# Relay_module.net
KiCad netlist of a schematic drawn in Altium Designer
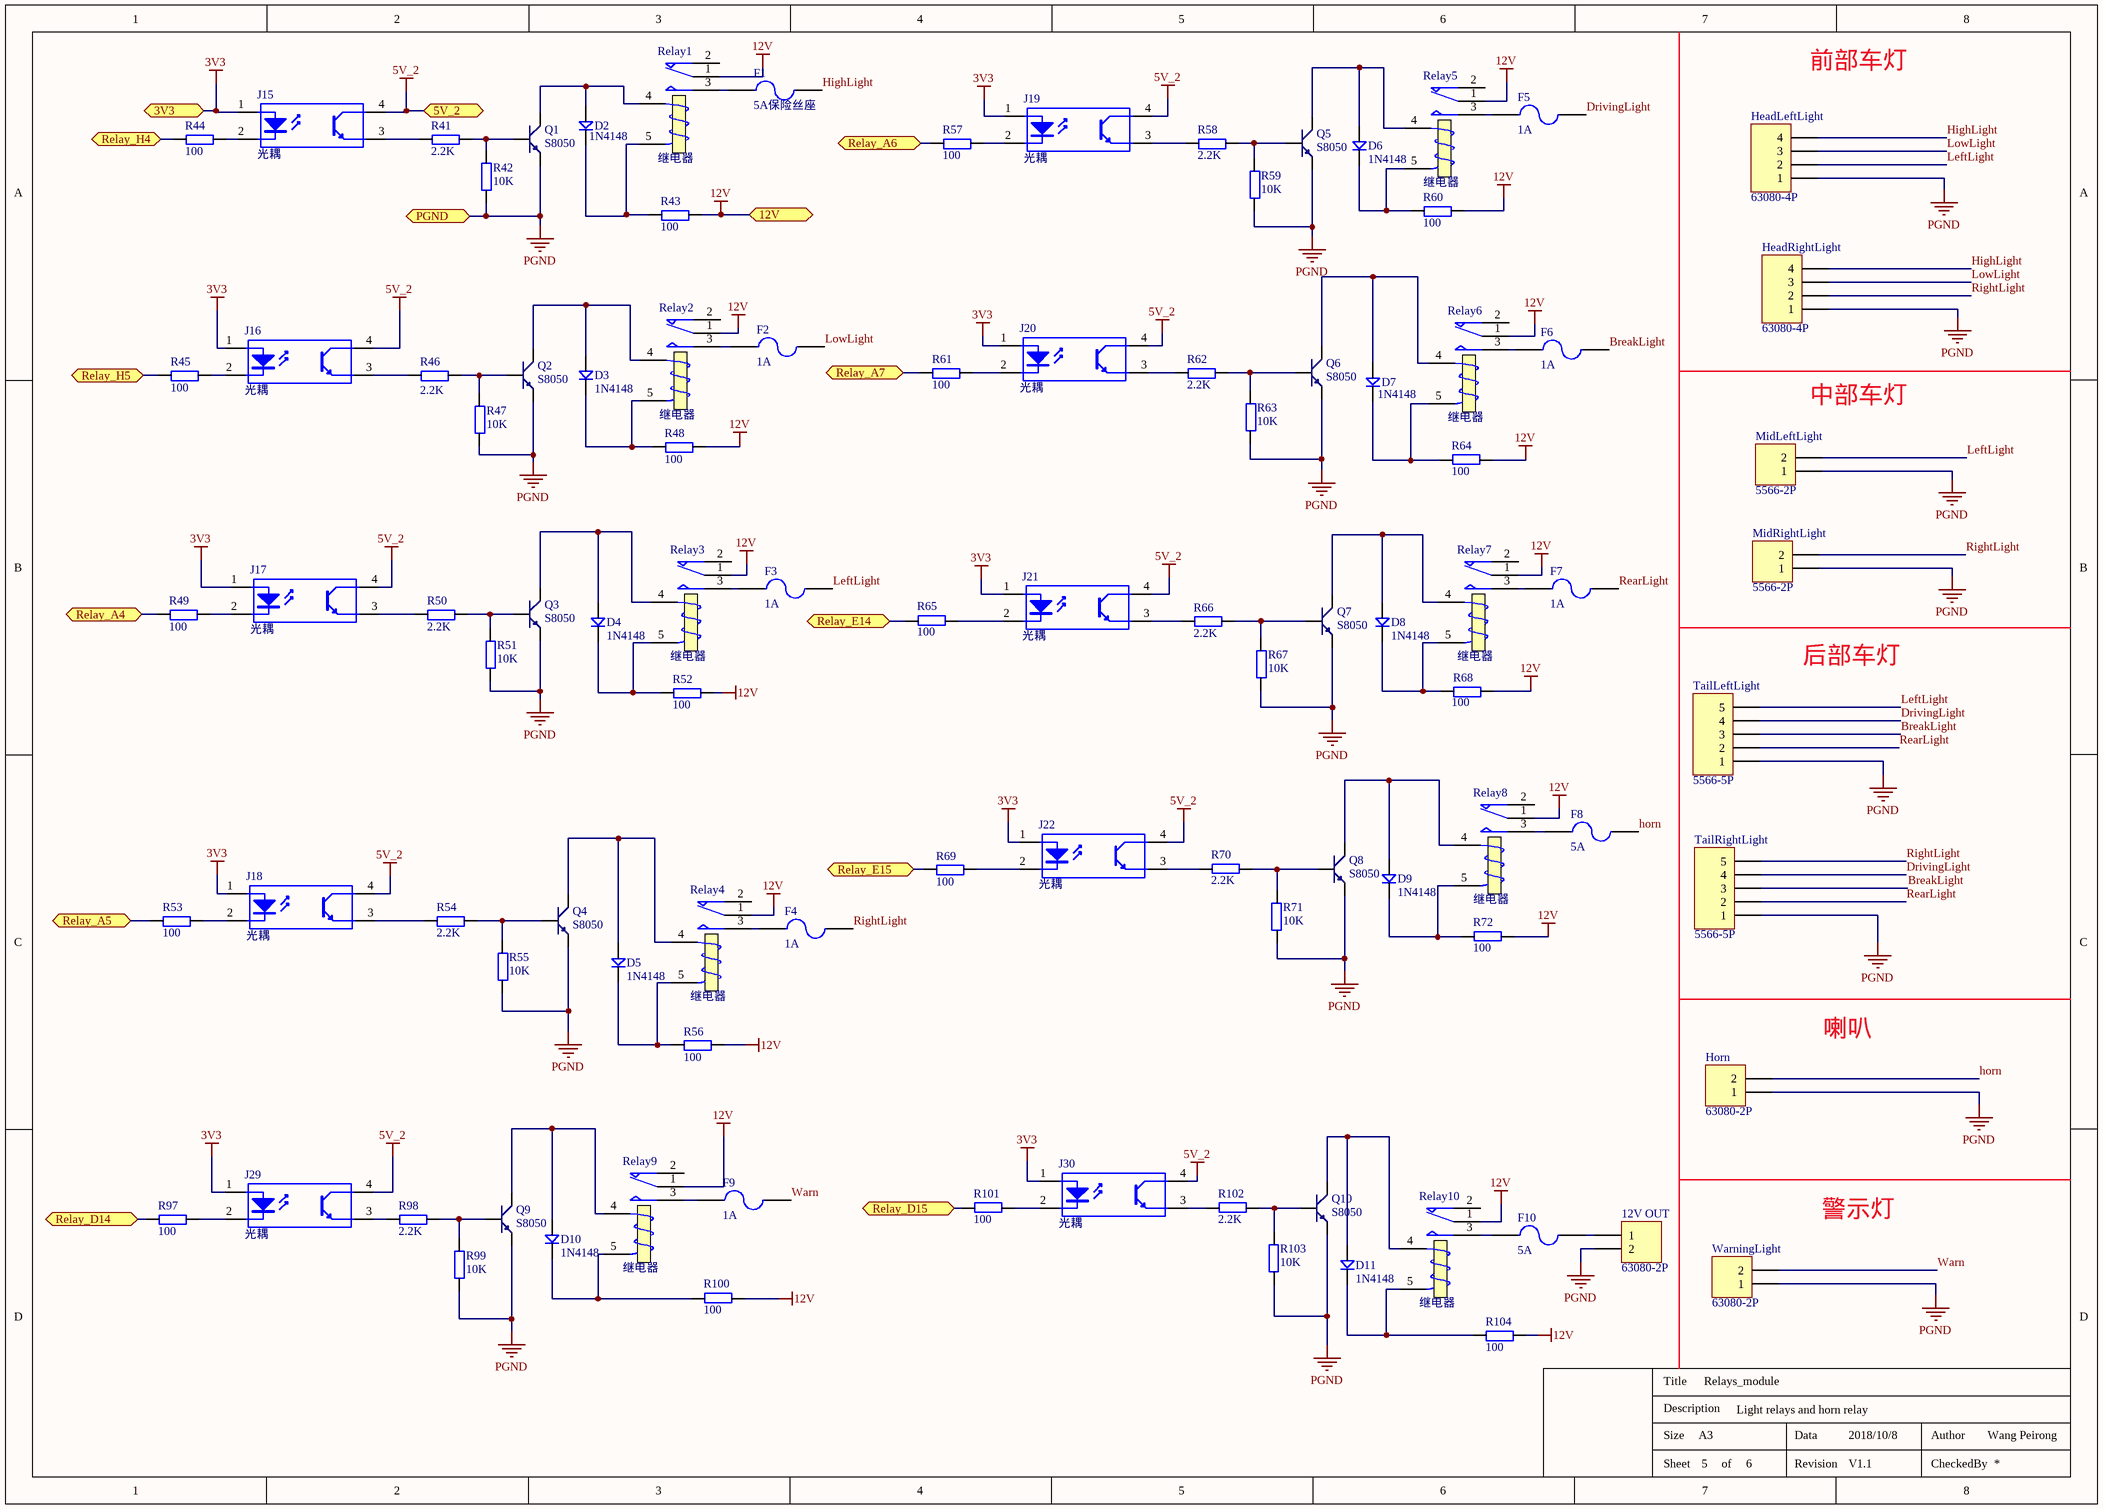
[diagram p0: Relay_module.SchDoc]

(export (version "E")
  (design (tool "Eeschema 10.0.6"))
  (components
    (comp (ref "12V OUT")
      (value "63080-2P")
      (footprint "63038-2P")
      (description "Header, 2-Pin")
      (fields (field (name "PUBLISHER") "Altium Limited"))
      (libsource (lib "") (part "Header 2_1"))
    )
    (comp (ref "D2")
      (value "1N4148")
      (footprint "DIODE_SOP")
      (libsource (lib "阿波罗STM32F4&F7底板封装库") (part "D"))
    )
    (comp (ref "D3")
      (value "1N4148")
      (footprint "DIODE_SOP")
      (libsource (lib "阿波罗STM32F4&F7底板封装库") (part "D"))
    )
    (comp (ref "D4")
      (value "1N4148")
      (footprint "DIODE_SOP")
      (libsource (lib "阿波罗STM32F4&F7底板封装库") (part "D"))
    )
    (comp (ref "D5")
      (value "1N4148")
      (footprint "DIODE_SOP")
      (libsource (lib "阿波罗STM32F4&F7底板封装库") (part "D"))
    )
    (comp (ref "D6")
      (value "1N4148")
      (footprint "DIODE_SOP")
      (libsource (lib "阿波罗STM32F4&F7底板封装库") (part "D"))
    )
    (comp (ref "D7")
      (value "1N4148")
      (footprint "DIODE_SOP")
      (libsource (lib "阿波罗STM32F4&F7底板封装库") (part "D"))
    )
    (comp (ref "D8")
      (value "1N4148")
      (footprint "DIODE_SOP")
      (libsource (lib "阿波罗STM32F4&F7底板封装库") (part "D"))
    )
    (comp (ref "D9")
      (value "1N4148")
      (footprint "DIODE_SOP")
      (libsource (lib "阿波罗STM32F4&F7底板封装库") (part "D"))
    )
    (comp (ref "D10")
      (value "1N4148")
      (footprint "DIODE_SOP")
      (libsource (lib "阿波罗STM32F4&F7底板封装库") (part "D"))
    )
    (comp (ref "D11")
      (value "1N4148")
      (footprint "DIODE_SOP")
      (libsource (lib "阿波罗STM32F4&F7底板封装库") (part "D"))
    )
    (comp (ref "F1")
      (value "5A保险丝座")
      (footprint "汽车保险丝座子")
      (fields (field (name "Comment") "5A") (field (name "PUBLISHER") "Altium Limited"))
      (libsource (lib "常用元件集成库") (part "保险丝"))
    )
    (comp (ref "F2")
      (value "1A")
      (footprint "汽车保险丝座子")
      (fields (field (name "Comment") "5A保险丝座") (field (name "PUBLISHER") "Altium Limited"))
      (libsource (lib "常用元件集成库") (part "保险丝"))
    )
    (comp (ref "F3")
      (value "1A")
      (footprint "汽车保险丝座子")
      (fields (field (name "Comment") "5A保险丝座") (field (name "PUBLISHER") "Altium Limited"))
      (libsource (lib "常用元件集成库") (part "保险丝"))
    )
    (comp (ref "F4")
      (value "1A")
      (footprint "汽车保险丝座子")
      (fields (field (name "Comment") "5A保险丝座") (field (name "PUBLISHER") "Altium Limited"))
      (libsource (lib "常用元件集成库") (part "保险丝"))
    )
    (comp (ref "F5")
      (value "1A")
      (footprint "汽车保险丝座子")
      (fields (field (name "Comment") "5A保险丝座") (field (name "PUBLISHER") "Altium Limited"))
      (libsource (lib "常用元件集成库") (part "保险丝"))
    )
    (comp (ref "F6")
      (value "1A")
      (footprint "汽车保险丝座子")
      (fields (field (name "Comment") "5A保险丝座") (field (name "PUBLISHER") "Altium Limited"))
      (libsource (lib "常用元件集成库") (part "保险丝"))
    )
    (comp (ref "F7")
      (value "1A")
      (footprint "汽车保险丝座子")
      (fields (field (name "Comment") "5A保险丝座") (field (name "PUBLISHER") "Altium Limited"))
      (libsource (lib "常用元件集成库") (part "保险丝"))
    )
    (comp (ref "F8")
      (value "5A")
      (footprint "汽车保险丝座子")
      (fields (field (name "Comment") "5A保险丝座") (field (name "PUBLISHER") "Altium Limited"))
      (libsource (lib "常用元件集成库") (part "保险丝"))
    )
    (comp (ref "F9")
      (value "1A")
      (footprint "汽车保险丝座子")
      (fields (field (name "Comment") "5A保险丝座") (field (name "PUBLISHER") "Altium Limited"))
      (libsource (lib "常用元件集成库") (part "保险丝"))
    )
    (comp (ref "F10")
      (value "5A")
      (footprint "汽车保险丝座子")
      (fields (field (name "Comment") "5A保险丝座") (field (name "PUBLISHER") "Altium Limited"))
      (libsource (lib "常用元件集成库") (part "保险丝"))
    )
    (comp (ref "HeadLeftLight")
      (value "63080-4P")
      (footprint "63080-4P")
      (description "Header, 4-Pin")
      (fields (field (name "PUBLISHER") "Altium Limited"))
      (libsource (lib "接插件集成库") (part "Header 4"))
    )
    (comp (ref "HeadRightLight")
      (value "63080-4P")
      (footprint "63080-4P")
      (description "Header, 4-Pin")
      (fields (field (name "PUBLISHER") "Altium Limited"))
      (libsource (lib "接插件集成库") (part "Header 4"))
    )
    (comp (ref "Horn")
      (value "63080-2P")
      (footprint "63038-2P")
      (description "Header, 2-Pin")
      (fields (field (name "PUBLISHER") "Altium Limited"))
      (libsource (lib "接插件集成库") (part "Header 2"))
    )
    (comp (ref "J15")
      (value "光耦")
      (footprint "SOP127P710X350-4N")
      (fields (field (name "PUBLISHER") "Altium Limited"))
      (libsource (lib "常用元件集成库") (part "光耦"))
    )
    (comp (ref "J16")
      (value "光耦")
      (footprint "SOP127P710X350-4N")
      (fields (field (name "PUBLISHER") "Altium Limited"))
      (libsource (lib "常用元件集成库") (part "光耦"))
    )
    (comp (ref "J17")
      (value "光耦")
      (footprint "SOP127P710X350-4N")
      (fields (field (name "PUBLISHER") "Altium Limited"))
      (libsource (lib "常用元件集成库") (part "光耦"))
    )
    (comp (ref "J18")
      (value "光耦")
      (footprint "SOP127P710X350-4N")
      (fields (field (name "PUBLISHER") "Altium Limited"))
      (libsource (lib "常用元件集成库") (part "光耦"))
    )
    (comp (ref "J19")
      (value "光耦")
      (footprint "SOP127P710X350-4N")
      (fields (field (name "PUBLISHER") "Altium Limited"))
      (libsource (lib "常用元件集成库") (part "光耦"))
    )
    (comp (ref "J20")
      (value "光耦")
      (footprint "SOP127P710X350-4N")
      (fields (field (name "PUBLISHER") "Altium Limited"))
      (libsource (lib "常用元件集成库") (part "光耦"))
    )
    (comp (ref "J21")
      (value "光耦")
      (footprint "SOP127P710X350-4N")
      (fields (field (name "PUBLISHER") "Altium Limited"))
      (libsource (lib "常用元件集成库") (part "光耦"))
    )
    (comp (ref "J22")
      (value "光耦")
      (footprint "SOP127P710X350-4N")
      (fields (field (name "PUBLISHER") "Altium Limited"))
      (libsource (lib "常用元件集成库") (part "光耦"))
    )
    (comp (ref "J29")
      (value "光耦")
      (footprint "SOP127P710X350-4N")
      (fields (field (name "PUBLISHER") "Altium Limited"))
      (libsource (lib "常用元件集成库") (part "光耦"))
    )
    (comp (ref "J30")
      (value "光耦")
      (footprint "SOP127P710X350-4N")
      (fields (field (name "PUBLISHER") "Altium Limited"))
      (libsource (lib "常用元件集成库") (part "光耦"))
    )
    (comp (ref "MidLeftLight")
      (value "5566-2P")
      (footprint "5566-2P")
      (description "Header, 2-Pin")
      (fields (field (name "PUBLISHER") "Altium Limited"))
      (libsource (lib "接插件集成库") (part "Header 2"))
    )
    (comp (ref "MidRightLight")
      (value "5566-2P")
      (footprint "5566-2P")
      (description "Header, 2-Pin")
      (fields (field (name "PUBLISHER") "Altium Limited"))
      (libsource (lib "接插件集成库") (part "Header 2"))
    )
    (comp (ref "Q1")
      (value "S8050")
      (footprint "SOT-23R")
      (description "8050/BCW846/BCW847")
      (libsource (lib "阿波罗STM32F4&F7底板封装库") (part "NPN"))
    )
    (comp (ref "Q2")
      (value "S8050")
      (footprint "SOT-23R")
      (description "8050/BCW846/BCW847")
      (libsource (lib "阿波罗STM32F4&F7底板封装库") (part "NPN"))
    )
    (comp (ref "Q3")
      (value "S8050")
      (footprint "SOT-23R")
      (description "8050/BCW846/BCW847")
      (libsource (lib "阿波罗STM32F4&F7底板封装库") (part "NPN"))
    )
    (comp (ref "Q4")
      (value "S8050")
      (footprint "SOT-23R")
      (description "8050/BCW846/BCW847")
      (libsource (lib "阿波罗STM32F4&F7底板封装库") (part "NPN"))
    )
    (comp (ref "Q5")
      (value "S8050")
      (footprint "SOT-23R")
      (description "8050/BCW846/BCW847")
      (libsource (lib "阿波罗STM32F4&F7底板封装库") (part "NPN"))
    )
    (comp (ref "Q6")
      (value "S8050")
      (footprint "SOT-23R")
      (description "8050/BCW846/BCW847")
      (libsource (lib "阿波罗STM32F4&F7底板封装库") (part "NPN"))
    )
    (comp (ref "Q7")
      (value "S8050")
      (footprint "SOT-23R")
      (description "8050/BCW846/BCW847")
      (libsource (lib "阿波罗STM32F4&F7底板封装库") (part "NPN"))
    )
    (comp (ref "Q8")
      (value "S8050")
      (footprint "SOT-23R")
      (description "8050/BCW846/BCW847")
      (libsource (lib "阿波罗STM32F4&F7底板封装库") (part "NPN"))
    )
    (comp (ref "Q9")
      (value "S8050")
      (footprint "SOT-23R")
      (description "8050/BCW846/BCW847")
      (libsource (lib "阿波罗STM32F4&F7底板封装库") (part "NPN"))
    )
    (comp (ref "Q10")
      (value "S8050")
      (footprint "SOT-23R")
      (description "8050/BCW846/BCW847")
      (libsource (lib "阿波罗STM32F4&F7底板封装库") (part "NPN"))
    )
    (comp (ref "R41") (value "2.2K") (footprint "0603P") (libsource (lib "阿波罗STM32F4&F7底板封装库") (part "R")))
    (comp (ref "R42") (value "10K") (footprint "0603P") (libsource (lib "阿波罗STM32F4&F7底板封装库") (part "R")))
    (comp (ref "R43") (value "100") (footprint "0603P") (libsource (lib "阿波罗STM32F4&F7底板封装库") (part "R")))
    (comp (ref "R44") (value "100") (footprint "0603P") (libsource (lib "阿波罗STM32F4&F7底板封装库") (part "R")))
    (comp (ref "R45") (value "100") (footprint "0603P") (libsource (lib "阿波罗STM32F4&F7底板封装库") (part "R")))
    (comp (ref "R46") (value "2.2K") (footprint "0603P") (libsource (lib "阿波罗STM32F4&F7底板封装库") (part "R")))
    (comp (ref "R47") (value "10K") (footprint "0603P") (libsource (lib "阿波罗STM32F4&F7底板封装库") (part "R")))
    (comp (ref "R48") (value "100") (footprint "0603P") (libsource (lib "阿波罗STM32F4&F7底板封装库") (part "R")))
    (comp (ref "R49") (value "100") (footprint "0603P") (libsource (lib "阿波罗STM32F4&F7底板封装库") (part "R")))
    (comp (ref "R50") (value "2.2K") (footprint "0603P") (libsource (lib "阿波罗STM32F4&F7底板封装库") (part "R")))
    (comp (ref "R51") (value "10K") (footprint "0603P") (libsource (lib "阿波罗STM32F4&F7底板封装库") (part "R")))
    (comp (ref "R52") (value "100") (footprint "0603P") (libsource (lib "阿波罗STM32F4&F7底板封装库") (part "R")))
    (comp (ref "R53") (value "100") (footprint "0603P") (libsource (lib "阿波罗STM32F4&F7底板封装库") (part "R")))
    (comp (ref "R54") (value "2.2K") (footprint "0603P") (libsource (lib "阿波罗STM32F4&F7底板封装库") (part "R")))
    (comp (ref "R55") (value "10K") (footprint "0603P") (libsource (lib "阿波罗STM32F4&F7底板封装库") (part "R")))
    (comp (ref "R56") (value "100") (footprint "0603P") (libsource (lib "阿波罗STM32F4&F7底板封装库") (part "R")))
    (comp (ref "R57") (value "100") (footprint "0603P") (libsource (lib "阿波罗STM32F4&F7底板封装库") (part "R")))
    (comp (ref "R58") (value "2.2K") (footprint "0603P") (libsource (lib "阿波罗STM32F4&F7底板封装库") (part "R")))
    (comp (ref "R59") (value "10K") (footprint "0603P") (libsource (lib "阿波罗STM32F4&F7底板封装库") (part "R")))
    (comp (ref "R60") (value "100") (footprint "0603P") (libsource (lib "阿波罗STM32F4&F7底板封装库") (part "R")))
    (comp (ref "R61") (value "100") (footprint "0603P") (libsource (lib "阿波罗STM32F4&F7底板封装库") (part "R")))
    (comp (ref "R62") (value "2.2K") (footprint "0603P") (libsource (lib "阿波罗STM32F4&F7底板封装库") (part "R")))
    (comp (ref "R63") (value "10K") (footprint "0603P") (libsource (lib "阿波罗STM32F4&F7底板封装库") (part "R")))
    (comp (ref "R64") (value "100") (footprint "0603P") (libsource (lib "阿波罗STM32F4&F7底板封装库") (part "R")))
    (comp (ref "R65") (value "100") (footprint "0603P") (libsource (lib "阿波罗STM32F4&F7底板封装库") (part "R")))
    (comp (ref "R66") (value "2.2K") (footprint "0603P") (libsource (lib "阿波罗STM32F4&F7底板封装库") (part "R")))
    (comp (ref "R67") (value "10K") (footprint "0603P") (libsource (lib "阿波罗STM32F4&F7底板封装库") (part "R")))
    (comp (ref "R68") (value "100") (footprint "0603P") (libsource (lib "阿波罗STM32F4&F7底板封装库") (part "R")))
    (comp (ref "R69") (value "100") (footprint "0603P") (libsource (lib "阿波罗STM32F4&F7底板封装库") (part "R")))
    (comp (ref "R70") (value "2.2K") (footprint "0603P") (libsource (lib "阿波罗STM32F4&F7底板封装库") (part "R")))
    (comp (ref "R71") (value "10K") (footprint "0603P") (libsource (lib "阿波罗STM32F4&F7底板封装库") (part "R")))
    (comp (ref "R72") (value "100") (footprint "0603P") (libsource (lib "阿波罗STM32F4&F7底板封装库") (part "R")))
    (comp (ref "R97") (value "100") (footprint "0603P") (libsource (lib "阿波罗STM32F4&F7底板封装库") (part "R")))
    (comp (ref "R98") (value "2.2K") (footprint "0603P") (libsource (lib "阿波罗STM32F4&F7底板封装库") (part "R")))
    (comp (ref "R99") (value "10K") (footprint "0603P") (libsource (lib "阿波罗STM32F4&F7底板封装库") (part "R")))
    (comp (ref "R100") (value "100") (footprint "0603P") (libsource (lib "阿波罗STM32F4&F7底板封装库") (part "R")))
    (comp (ref "R101") (value "100") (footprint "0603P") (libsource (lib "阿波罗STM32F4&F7底板封装库") (part "R")))
    (comp (ref "R102") (value "2.2K") (footprint "0603P") (libsource (lib "阿波罗STM32F4&F7底板封装库") (part "R")))
    (comp (ref "R103") (value "10K") (footprint "0603P") (libsource (lib "阿波罗STM32F4&F7底板封装库") (part "R")))
    (comp (ref "R104") (value "100") (footprint "0603P") (libsource (lib "阿波罗STM32F4&F7底板封装库") (part "R")))
    (comp (ref "Relay1") (value "继电器") (footprint "SRD-12VDC") (libsource (lib "常用元件集成库") (part "继电器")))
    (comp (ref "Relay2") (value "继电器") (footprint "SRD-12VDC") (libsource (lib "常用元件集成库") (part "继电器")))
    (comp (ref "Relay3") (value "继电器") (footprint "SRD-12VDC") (libsource (lib "常用元件集成库") (part "继电器")))
    (comp (ref "Relay4") (value "继电器") (footprint "SRD-12VDC") (libsource (lib "常用元件集成库") (part "继电器")))
    (comp (ref "Relay5") (value "继电器") (footprint "SRD-12VDC") (libsource (lib "常用元件集成库") (part "继电器")))
    (comp (ref "Relay6") (value "继电器") (footprint "SRD-12VDC") (libsource (lib "常用元件集成库") (part "继电器")))
    (comp (ref "Relay7") (value "继电器") (footprint "SRD-12VDC") (libsource (lib "常用元件集成库") (part "继电器")))
    (comp (ref "Relay8") (value "继电器") (footprint "SRD-12VDC") (libsource (lib "常用元件集成库") (part "继电器")))
    (comp (ref "Relay9") (value "继电器") (footprint "SRD-12VDC") (libsource (lib "常用元件集成库") (part "继电器")))
    (comp (ref "Relay10") (value "继电器") (footprint "SRD-12VDC") (libsource (lib "常用元件集成库") (part "继电器")))
    (comp (ref "TailLeftLight")
      (value "5566-5P")
      (footprint "5566-5P")
      (description "Header, 5-Pin")
      (fields (field (name "PUBLISHER") "Altium Limited"))
      (libsource (lib "接插件集成库") (part "Header 5"))
    )
    (comp (ref "TailRightLight")
      (value "5566-5P")
      (footprint "5566-5P")
      (description "Header, 5-Pin")
      (fields (field (name "PUBLISHER") "Altium Limited"))
      (libsource (lib "接插件集成库") (part "Header 5"))
    )
    (comp (ref "WarningLight")
      (value "63080-2P")
      (footprint "63038-2P")
      (description "Header, 2-Pin")
      (fields (field (name "PUBLISHER") "Altium Limited"))
      (libsource (lib "接插件集成库") (part "Header 2"))
    )
  )
  (nets
    (net (code "1") (name "/BreakLight") (class "Default")
      (node (ref "F6") (pin "2") (pinfunction "2_2") (pintype "passive"))
      (node (ref "TailLeftLight") (pin "3") (pinfunction "3_3") (pintype "passive"))
      (node (ref "TailRightLight") (pin "3") (pinfunction "3_3") (pintype "passive"))
    )
    (net (code "2") (name "/DrivingLight") (class "Default")
      (node (ref "F5") (pin "2") (pinfunction "2_2") (pintype "passive"))
      (node (ref "TailLeftLight") (pin "4") (pinfunction "4_4") (pintype "passive"))
      (node (ref "TailRightLight") (pin "4") (pinfunction "4_4") (pintype "passive"))
    )
    (net (code "3") (name "/HighLight") (class "Default")
      (node (ref "F1") (pin "2") (pinfunction "2_2") (pintype "passive"))
      (node (ref "HeadLeftLight") (pin "4") (pinfunction "4_4") (pintype "passive"))
      (node (ref "HeadRightLight") (pin "4") (pinfunction "4_4") (pintype "passive"))
    )
    (net (code "4") (name "/LeftLight") (class "Default")
      (node (ref "F3") (pin "2") (pinfunction "2_2") (pintype "passive"))
      (node (ref "HeadLeftLight") (pin "2") (pinfunction "2_2") (pintype "passive"))
      (node (ref "MidLeftLight") (pin "2") (pinfunction "2_2") (pintype "passive"))
      (node (ref "TailLeftLight") (pin "5") (pinfunction "5_5") (pintype "passive"))
    )
    (net (code "5") (name "/LowLight") (class "Default")
      (node (ref "F2") (pin "2") (pinfunction "2_2") (pintype "passive"))
      (node (ref "HeadLeftLight") (pin "3") (pinfunction "3_3") (pintype "passive"))
      (node (ref "HeadRightLight") (pin "3") (pinfunction "3_3") (pintype "passive"))
    )
    (net (code "6") (name "/RearLight") (class "Default")
      (node (ref "F7") (pin "2") (pinfunction "2_2") (pintype "passive"))
      (node (ref "TailLeftLight") (pin "2") (pinfunction "2_2") (pintype "passive"))
      (node (ref "TailRightLight") (pin "2") (pinfunction "2_2") (pintype "passive"))
    )
    (net (code "7") (name "/Relay_A4") (class "Default") (node (ref "R49") (pin "1") (pintype "passive")))
    (net (code "8") (name "/Relay_A5") (class "Default") (node (ref "R53") (pin "1") (pintype "passive")))
    (net (code "9") (name "/Relay_A6") (class "Default") (node (ref "R57") (pin "1") (pintype "passive")))
    (net (code "10") (name "/Relay_A7") (class "Default") (node (ref "R61") (pin "1") (pintype "passive")))
    (net (code "11") (name "/Relay_D14") (class "Default") (node (ref "R97") (pin "1") (pintype "passive")))
    (net (code "12") (name "/Relay_D15") (class "Default") (node (ref "R101") (pin "2") (pintype "passive")))
    (net (code "13") (name "/Relay_E14") (class "Default") (node (ref "R65") (pin "2") (pintype "passive")))
    (net (code "14") (name "/Relay_E15") (class "Default") (node (ref "R69") (pin "1") (pintype "passive")))
    (net (code "15") (name "/Relay_H4") (class "Default") (node (ref "R44") (pin "1") (pintype "passive")))
    (net (code "16") (name "/Relay_H5") (class "Default") (node (ref "R45") (pin "1") (pintype "passive")))
    (net (code "17") (name "/RightLight") (class "Default")
      (node (ref "F4") (pin "2") (pinfunction "2_2") (pintype "passive"))
      (node (ref "HeadRightLight") (pin "2") (pinfunction "2_2") (pintype "passive"))
      (node (ref "MidRightLight") (pin "2") (pinfunction "2_2") (pintype "passive"))
      (node (ref "TailRightLight") (pin "5") (pinfunction "5_5") (pintype "passive"))
    )
    (net (code "18") (name "/Warn") (class "Default")
      (node (ref "F9") (pin "2") (pinfunction "2_2") (pintype "passive"))
      (node (ref "WarningLight") (pin "2") (pinfunction "2_2") (pintype "passive"))
    )
    (net (code "19") (name "/horn") (class "Default")
      (node (ref "F8") (pin "2") (pinfunction "2_2") (pintype "passive"))
      (node (ref "Horn") (pin "2") (pinfunction "2_2") (pintype "passive"))
    )
    (net (code "20") (name "3V3") (class "Default")
      (node (ref "J15") (pin "1") (pinfunction "A_1") (pintype "passive"))
      (node (ref "J16") (pin "1") (pinfunction "A_1") (pintype "passive"))
      (node (ref "J17") (pin "1") (pinfunction "A_1") (pintype "passive"))
      (node (ref "J18") (pin "1") (pinfunction "A_1") (pintype "passive"))
      (node (ref "J19") (pin "1") (pinfunction "A_1") (pintype "passive"))
      (node (ref "J20") (pin "1") (pinfunction "A_1") (pintype "passive"))
      (node (ref "J21") (pin "1") (pinfunction "A_1") (pintype "passive"))
      (node (ref "J22") (pin "1") (pinfunction "A_1") (pintype "passive"))
      (node (ref "J29") (pin "1") (pinfunction "A_1") (pintype "passive"))
      (node (ref "J30") (pin "1") (pinfunction "A_1") (pintype "passive"))
    )
    (net (code "21") (name "5V_2") (class "Default")
      (node (ref "J15") (pin "4") (pinfunction "C_4") (pintype "passive"))
      (node (ref "J16") (pin "4") (pinfunction "C_4") (pintype "passive"))
      (node (ref "J17") (pin "4") (pinfunction "C_4") (pintype "passive"))
      (node (ref "J18") (pin "4") (pinfunction "C_4") (pintype "passive"))
      (node (ref "J19") (pin "4") (pinfunction "C_4") (pintype "passive"))
      (node (ref "J20") (pin "4") (pinfunction "C_4") (pintype "passive"))
      (node (ref "J21") (pin "4") (pinfunction "C_4") (pintype "passive"))
      (node (ref "J22") (pin "4") (pinfunction "C_4") (pintype "passive"))
      (node (ref "J29") (pin "4") (pinfunction "C_4") (pintype "passive"))
      (node (ref "J30") (pin "4") (pinfunction "C_4") (pintype "passive"))
    )
    (net (code "22") (name "12V") (class "Default")
      (node (ref "R100") (pin "1") (pintype "passive"))
      (node (ref "R104") (pin "2") (pintype "passive"))
      (node (ref "R43") (pin "2") (pintype "passive"))
      (node (ref "R48") (pin "2") (pintype "passive"))
      (node (ref "R52") (pin "2") (pintype "passive"))
      (node (ref "R56") (pin "2") (pintype "passive"))
      (node (ref "R60") (pin "2") (pintype "passive"))
      (node (ref "R64") (pin "1") (pintype "passive"))
      (node (ref "R68") (pin "2") (pintype "passive"))
      (node (ref "R72") (pin "1") (pintype "passive"))
      (node (ref "Relay1") (pin "1") (pinfunction "COM_1") (pintype "passive"))
      (node (ref "Relay10") (pin "1") (pinfunction "COM_1") (pintype "passive"))
      (node (ref "Relay2") (pin "1") (pinfunction "COM_1") (pintype "passive"))
      (node (ref "Relay3") (pin "1") (pinfunction "COM_1") (pintype "passive"))
      (node (ref "Relay4") (pin "1") (pinfunction "COM_1") (pintype "passive"))
      (node (ref "Relay5") (pin "1") (pinfunction "COM_1") (pintype "passive"))
      (node (ref "Relay6") (pin "1") (pinfunction "COM_1") (pintype "passive"))
      (node (ref "Relay7") (pin "1") (pinfunction "COM_1") (pintype "passive"))
      (node (ref "Relay8") (pin "1") (pinfunction "COM_1") (pintype "passive"))
      (node (ref "Relay9") (pin "1") (pinfunction "COM_1") (pintype "passive"))
    )
    (net (code "23") (name "Net-(12V OUT-Pad1)") (class "Default")
      (node (ref "12V OUT") (pin "1") (pinfunction "1_1") (pintype "passive"))
      (node (ref "F10") (pin "2") (pinfunction "2_2") (pintype "passive"))
    )
    (net (code "24") (name "Net-(J15-E)") (class "Default")
      (node (ref "J15") (pin "3") (pinfunction "E_3") (pintype "passive"))
      (node (ref "R41") (pin "1") (pintype "passive"))
    )
    (net (code "25") (name "Net-(J15-K)") (class "Default")
      (node (ref "J15") (pin "2") (pinfunction "K_2") (pintype "passive"))
      (node (ref "R44") (pin "2") (pintype "passive"))
    )
    (net (code "26") (name "Net-(J16-E)") (class "Default")
      (node (ref "J16") (pin "3") (pinfunction "E_3") (pintype "passive"))
      (node (ref "R46") (pin "1") (pintype "passive"))
    )
    (net (code "27") (name "Net-(J16-K)") (class "Default")
      (node (ref "J16") (pin "2") (pinfunction "K_2") (pintype "passive"))
      (node (ref "R45") (pin "2") (pintype "passive"))
    )
    (net (code "28") (name "Net-(J17-E)") (class "Default")
      (node (ref "J17") (pin "3") (pinfunction "E_3") (pintype "passive"))
      (node (ref "R50") (pin "1") (pintype "passive"))
    )
    (net (code "29") (name "Net-(J17-K)") (class "Default")
      (node (ref "J17") (pin "2") (pinfunction "K_2") (pintype "passive"))
      (node (ref "R49") (pin "2") (pintype "passive"))
    )
    (net (code "30") (name "Net-(J18-E)") (class "Default")
      (node (ref "J18") (pin "3") (pinfunction "E_3") (pintype "passive"))
      (node (ref "R54") (pin "1") (pintype "passive"))
    )
    (net (code "31") (name "Net-(J18-K)") (class "Default")
      (node (ref "J18") (pin "2") (pinfunction "K_2") (pintype "passive"))
      (node (ref "R53") (pin "2") (pintype "passive"))
    )
    (net (code "32") (name "Net-(J19-E)") (class "Default")
      (node (ref "J19") (pin "3") (pinfunction "E_3") (pintype "passive"))
      (node (ref "R58") (pin "1") (pintype "passive"))
    )
    (net (code "33") (name "Net-(J19-K)") (class "Default")
      (node (ref "J19") (pin "2") (pinfunction "K_2") (pintype "passive"))
      (node (ref "R57") (pin "2") (pintype "passive"))
    )
    (net (code "34") (name "Net-(J20-E)") (class "Default")
      (node (ref "J20") (pin "3") (pinfunction "E_3") (pintype "passive"))
      (node (ref "R62") (pin "1") (pintype "passive"))
    )
    (net (code "35") (name "Net-(J20-K)") (class "Default")
      (node (ref "J20") (pin "2") (pinfunction "K_2") (pintype "passive"))
      (node (ref "R61") (pin "2") (pintype "passive"))
    )
    (net (code "36") (name "Net-(J21-E)") (class "Default")
      (node (ref "J21") (pin "3") (pinfunction "E_3") (pintype "passive"))
      (node (ref "R66") (pin "1") (pintype "passive"))
    )
    (net (code "37") (name "Net-(J21-K)") (class "Default")
      (node (ref "J21") (pin "2") (pinfunction "K_2") (pintype "passive"))
      (node (ref "R65") (pin "1") (pintype "passive"))
    )
    (net (code "38") (name "Net-(J22-E)") (class "Default")
      (node (ref "J22") (pin "3") (pinfunction "E_3") (pintype "passive"))
      (node (ref "R70") (pin "2") (pintype "passive"))
    )
    (net (code "39") (name "Net-(J22-K)") (class "Default")
      (node (ref "J22") (pin "2") (pinfunction "K_2") (pintype "passive"))
      (node (ref "R69") (pin "2") (pintype "passive"))
    )
    (net (code "40") (name "Net-(J29-E)") (class "Default")
      (node (ref "J29") (pin "3") (pinfunction "E_3") (pintype "passive"))
      (node (ref "R98") (pin "1") (pintype "passive"))
    )
    (net (code "41") (name "Net-(J29-K)") (class "Default")
      (node (ref "J29") (pin "2") (pinfunction "K_2") (pintype "passive"))
      (node (ref "R97") (pin "2") (pintype "passive"))
    )
    (net (code "42") (name "Net-(J30-E)") (class "Default")
      (node (ref "J30") (pin "3") (pinfunction "E_3") (pintype "passive"))
      (node (ref "R102") (pin "2") (pintype "passive"))
    )
    (net (code "43") (name "Net-(J30-K)") (class "Default")
      (node (ref "J30") (pin "2") (pinfunction "K_2") (pintype "passive"))
      (node (ref "R101") (pin "1") (pintype "passive"))
    )
    (net (code "44") (name "Net-(Q1-B)") (class "Default")
      (node (ref "Q1") (pin "2") (pinfunction "B_2") (pintype "passive"))
      (node (ref "R41") (pin "2") (pintype "passive"))
      (node (ref "R42") (pin "2") (pintype "passive"))
    )
    (net (code "45") (name "Net-(Q1-C)") (class "Default")
      (node (ref "D2") (pin "1") (pintype "passive"))
      (node (ref "Q1") (pin "3") (pinfunction "C_3") (pintype "passive"))
      (node (ref "Relay1") (pin "4") (pinfunction "T1_4") (pintype "passive"))
    )
    (net (code "46") (name "Net-(Q2-B)") (class "Default")
      (node (ref "Q2") (pin "2") (pinfunction "B_2") (pintype "passive"))
      (node (ref "R46") (pin "2") (pintype "passive"))
      (node (ref "R47") (pin "2") (pintype "passive"))
    )
    (net (code "47") (name "Net-(Q2-C)") (class "Default")
      (node (ref "D3") (pin "1") (pintype "passive"))
      (node (ref "Q2") (pin "3") (pinfunction "C_3") (pintype "passive"))
      (node (ref "Relay2") (pin "4") (pinfunction "T1_4") (pintype "passive"))
    )
    (net (code "48") (name "Net-(Q3-B)") (class "Default")
      (node (ref "Q3") (pin "2") (pinfunction "B_2") (pintype "passive"))
      (node (ref "R50") (pin "2") (pintype "passive"))
      (node (ref "R51") (pin "2") (pintype "passive"))
    )
    (net (code "49") (name "Net-(Q3-C)") (class "Default")
      (node (ref "D4") (pin "1") (pintype "passive"))
      (node (ref "Q3") (pin "3") (pinfunction "C_3") (pintype "passive"))
      (node (ref "Relay3") (pin "4") (pinfunction "T1_4") (pintype "passive"))
    )
    (net (code "50") (name "Net-(Q4-B)") (class "Default")
      (node (ref "Q4") (pin "2") (pinfunction "B_2") (pintype "passive"))
      (node (ref "R54") (pin "2") (pintype "passive"))
      (node (ref "R55") (pin "2") (pintype "passive"))
    )
    (net (code "51") (name "Net-(Q4-C)") (class "Default")
      (node (ref "D5") (pin "1") (pintype "passive"))
      (node (ref "Q4") (pin "3") (pinfunction "C_3") (pintype "passive"))
      (node (ref "Relay4") (pin "4") (pinfunction "T1_4") (pintype "passive"))
    )
    (net (code "52") (name "Net-(Q5-B)") (class "Default")
      (node (ref "Q5") (pin "2") (pinfunction "B_2") (pintype "passive"))
      (node (ref "R58") (pin "2") (pintype "passive"))
      (node (ref "R59") (pin "2") (pintype "passive"))
    )
    (net (code "53") (name "Net-(Q5-C)") (class "Default")
      (node (ref "D6") (pin "1") (pintype "passive"))
      (node (ref "Q5") (pin "3") (pinfunction "C_3") (pintype "passive"))
      (node (ref "Relay5") (pin "4") (pinfunction "T1_4") (pintype "passive"))
    )
    (net (code "54") (name "Net-(Q6-B)") (class "Default")
      (node (ref "Q6") (pin "2") (pinfunction "B_2") (pintype "passive"))
      (node (ref "R62") (pin "2") (pintype "passive"))
      (node (ref "R63") (pin "2") (pintype "passive"))
    )
    (net (code "55") (name "Net-(Q6-C)") (class "Default")
      (node (ref "D7") (pin "1") (pintype "passive"))
      (node (ref "Q6") (pin "3") (pinfunction "C_3") (pintype "passive"))
      (node (ref "Relay6") (pin "4") (pinfunction "T1_4") (pintype "passive"))
    )
    (net (code "56") (name "Net-(Q7-B)") (class "Default")
      (node (ref "Q7") (pin "2") (pinfunction "B_2") (pintype "passive"))
      (node (ref "R66") (pin "2") (pintype "passive"))
      (node (ref "R67") (pin "2") (pintype "passive"))
    )
    (net (code "57") (name "Net-(Q7-C)") (class "Default")
      (node (ref "D8") (pin "1") (pintype "passive"))
      (node (ref "Q7") (pin "3") (pinfunction "C_3") (pintype "passive"))
      (node (ref "Relay7") (pin "4") (pinfunction "T1_4") (pintype "passive"))
    )
    (net (code "58") (name "Net-(Q8-B)") (class "Default")
      (node (ref "Q8") (pin "2") (pinfunction "B_2") (pintype "passive"))
      (node (ref "R70") (pin "1") (pintype "passive"))
      (node (ref "R71") (pin "1") (pintype "passive"))
    )
    (net (code "59") (name "Net-(Q8-C)") (class "Default")
      (node (ref "D9") (pin "1") (pintype "passive"))
      (node (ref "Q8") (pin "3") (pinfunction "C_3") (pintype "passive"))
      (node (ref "Relay8") (pin "4") (pinfunction "T1_4") (pintype "passive"))
    )
    (net (code "60") (name "Net-(Q9-B)") (class "Default")
      (node (ref "Q9") (pin "2") (pinfunction "B_2") (pintype "passive"))
      (node (ref "R98") (pin "2") (pintype "passive"))
      (node (ref "R99") (pin "2") (pintype "passive"))
    )
    (net (code "61") (name "Net-(Q9-C)") (class "Default")
      (node (ref "D10") (pin "1") (pintype "passive"))
      (node (ref "Q9") (pin "3") (pinfunction "C_3") (pintype "passive"))
      (node (ref "Relay9") (pin "4") (pinfunction "T1_4") (pintype "passive"))
    )
    (net (code "62") (name "Net-(Q10-B)") (class "Default")
      (node (ref "Q10") (pin "2") (pinfunction "B_2") (pintype "passive"))
      (node (ref "R102") (pin "1") (pintype "passive"))
      (node (ref "R103") (pin "1") (pintype "passive"))
    )
    (net (code "63") (name "Net-(Q10-C)") (class "Default")
      (node (ref "D11") (pin "1") (pintype "passive"))
      (node (ref "Q10") (pin "3") (pinfunction "C_3") (pintype "passive"))
      (node (ref "Relay10") (pin "4") (pinfunction "T1_4") (pintype "passive"))
    )
    (net (code "64") (name "Net-(Relay1-NO)") (class "Default")
      (node (ref "F1") (pin "1") (pinfunction "1_1") (pintype "passive"))
      (node (ref "Relay1") (pin "3") (pinfunction "NO_3") (pintype "passive"))
    )
    (net (code "65") (name "Net-(Relay1-T2)") (class "Default")
      (node (ref "D2") (pin "2") (pintype "passive"))
      (node (ref "R43") (pin "1") (pintype "passive"))
      (node (ref "Relay1") (pin "5") (pinfunction "T2_5") (pintype "passive"))
    )
    (net (code "66") (name "Net-(Relay2-NO)") (class "Default")
      (node (ref "F2") (pin "1") (pinfunction "1_1") (pintype "passive"))
      (node (ref "Relay2") (pin "3") (pinfunction "NO_3") (pintype "passive"))
    )
    (net (code "67") (name "Net-(Relay2-T2)") (class "Default")
      (node (ref "D3") (pin "2") (pintype "passive"))
      (node (ref "R48") (pin "1") (pintype "passive"))
      (node (ref "Relay2") (pin "5") (pinfunction "T2_5") (pintype "passive"))
    )
    (net (code "68") (name "Net-(Relay3-NO)") (class "Default")
      (node (ref "F3") (pin "1") (pinfunction "1_1") (pintype "passive"))
      (node (ref "Relay3") (pin "3") (pinfunction "NO_3") (pintype "passive"))
    )
    (net (code "69") (name "Net-(Relay3-T2)") (class "Default")
      (node (ref "D4") (pin "2") (pintype "passive"))
      (node (ref "R52") (pin "1") (pintype "passive"))
      (node (ref "Relay3") (pin "5") (pinfunction "T2_5") (pintype "passive"))
    )
    (net (code "70") (name "Net-(Relay4-NO)") (class "Default")
      (node (ref "F4") (pin "1") (pinfunction "1_1") (pintype "passive"))
      (node (ref "Relay4") (pin "3") (pinfunction "NO_3") (pintype "passive"))
    )
    (net (code "71") (name "Net-(Relay4-T2)") (class "Default")
      (node (ref "D5") (pin "2") (pintype "passive"))
      (node (ref "R56") (pin "1") (pintype "passive"))
      (node (ref "Relay4") (pin "5") (pinfunction "T2_5") (pintype "passive"))
    )
    (net (code "72") (name "Net-(Relay5-NO)") (class "Default")
      (node (ref "F5") (pin "1") (pinfunction "1_1") (pintype "passive"))
      (node (ref "Relay5") (pin "3") (pinfunction "NO_3") (pintype "passive"))
    )
    (net (code "73") (name "Net-(Relay5-T2)") (class "Default")
      (node (ref "D6") (pin "2") (pintype "passive"))
      (node (ref "R60") (pin "1") (pintype "passive"))
      (node (ref "Relay5") (pin "5") (pinfunction "T2_5") (pintype "passive"))
    )
    (net (code "74") (name "Net-(Relay6-NO)") (class "Default")
      (node (ref "F6") (pin "1") (pinfunction "1_1") (pintype "passive"))
      (node (ref "Relay6") (pin "3") (pinfunction "NO_3") (pintype "passive"))
    )
    (net (code "75") (name "Net-(Relay6-T2)") (class "Default")
      (node (ref "D7") (pin "2") (pintype "passive"))
      (node (ref "R64") (pin "2") (pintype "passive"))
      (node (ref "Relay6") (pin "5") (pinfunction "T2_5") (pintype "passive"))
    )
    (net (code "76") (name "Net-(Relay7-NO)") (class "Default")
      (node (ref "F7") (pin "1") (pinfunction "1_1") (pintype "passive"))
      (node (ref "Relay7") (pin "3") (pinfunction "NO_3") (pintype "passive"))
    )
    (net (code "77") (name "Net-(Relay7-T2)") (class "Default")
      (node (ref "D8") (pin "2") (pintype "passive"))
      (node (ref "R68") (pin "1") (pintype "passive"))
      (node (ref "Relay7") (pin "5") (pinfunction "T2_5") (pintype "passive"))
    )
    (net (code "78") (name "Net-(Relay8-NO)") (class "Default")
      (node (ref "F8") (pin "1") (pinfunction "1_1") (pintype "passive"))
      (node (ref "Relay8") (pin "3") (pinfunction "NO_3") (pintype "passive"))
    )
    (net (code "79") (name "Net-(Relay8-T2)") (class "Default")
      (node (ref "D9") (pin "2") (pintype "passive"))
      (node (ref "R72") (pin "2") (pintype "passive"))
      (node (ref "Relay8") (pin "5") (pinfunction "T2_5") (pintype "passive"))
    )
    (net (code "80") (name "Net-(Relay9-NO)") (class "Default")
      (node (ref "F9") (pin "1") (pinfunction "1_1") (pintype "passive"))
      (node (ref "Relay9") (pin "3") (pinfunction "NO_3") (pintype "passive"))
    )
    (net (code "81") (name "Net-(Relay9-T2)") (class "Default")
      (node (ref "D10") (pin "2") (pintype "passive"))
      (node (ref "R100") (pin "2") (pintype "passive"))
      (node (ref "Relay9") (pin "5") (pinfunction "T2_5") (pintype "passive"))
    )
    (net (code "82") (name "Net-(Relay10-NO)") (class "Default")
      (node (ref "F10") (pin "1") (pinfunction "1_1") (pintype "passive"))
      (node (ref "Relay10") (pin "3") (pinfunction "NO_3") (pintype "passive"))
    )
    (net (code "83") (name "Net-(Relay10-T2)") (class "Default")
      (node (ref "D11") (pin "2") (pintype "passive"))
      (node (ref "R104") (pin "1") (pintype "passive"))
      (node (ref "Relay10") (pin "5") (pinfunction "T2_5") (pintype "passive"))
    )
    (net (code "84") (name "PGND") (class "Default")
      (node (ref "12V OUT") (pin "2") (pinfunction "2_2") (pintype "passive"))
      (node (ref "HeadLeftLight") (pin "1") (pinfunction "1_1") (pintype "passive"))
      (node (ref "HeadRightLight") (pin "1") (pinfunction "1_1") (pintype "passive"))
      (node (ref "Horn") (pin "1") (pinfunction "1_1") (pintype "passive"))
      (node (ref "MidLeftLight") (pin "1") (pinfunction "1_1") (pintype "passive"))
      (node (ref "MidRightLight") (pin "1") (pinfunction "1_1") (pintype "passive"))
      (node (ref "Q1") (pin "1") (pinfunction "E_1") (pintype "passive"))
      (node (ref "Q10") (pin "1") (pinfunction "E_1") (pintype "passive"))
      (node (ref "Q2") (pin "1") (pinfunction "E_1") (pintype "passive"))
      (node (ref "Q3") (pin "1") (pinfunction "E_1") (pintype "passive"))
      (node (ref "Q4") (pin "1") (pinfunction "E_1") (pintype "passive"))
      (node (ref "Q5") (pin "1") (pinfunction "E_1") (pintype "passive"))
      (node (ref "Q6") (pin "1") (pinfunction "E_1") (pintype "passive"))
      (node (ref "Q7") (pin "1") (pinfunction "E_1") (pintype "passive"))
      (node (ref "Q8") (pin "1") (pinfunction "E_1") (pintype "passive"))
      (node (ref "Q9") (pin "1") (pinfunction "E_1") (pintype "passive"))
      (node (ref "R103") (pin "2") (pintype "passive"))
      (node (ref "R42") (pin "1") (pintype "passive"))
      (node (ref "R47") (pin "1") (pintype "passive"))
      (node (ref "R51") (pin "1") (pintype "passive"))
      (node (ref "R55") (pin "1") (pintype "passive"))
      (node (ref "R59") (pin "1") (pintype "passive"))
      (node (ref "R63") (pin "1") (pintype "passive"))
      (node (ref "R67") (pin "1") (pintype "passive"))
      (node (ref "R71") (pin "2") (pintype "passive"))
      (node (ref "R99") (pin "1") (pintype "passive"))
      (node (ref "TailLeftLight") (pin "1") (pinfunction "1_1") (pintype "passive"))
      (node (ref "TailRightLight") (pin "1") (pinfunction "1_1") (pintype "passive"))
      (node (ref "WarningLight") (pin "1") (pinfunction "1_1") (pintype "passive"))
    )
    (net (code "85") (name "unconnected-(Relay1-NC-Pad2)") (class "Default")
      (node (ref "Relay1") (pin "2") (pinfunction "NC_2") (pintype "passive"))
    )
    (net (code "86") (name "unconnected-(Relay2-NC-Pad2)") (class "Default")
      (node (ref "Relay2") (pin "2") (pinfunction "NC_2") (pintype "passive"))
    )
    (net (code "87") (name "unconnected-(Relay3-NC-Pad2)") (class "Default")
      (node (ref "Relay3") (pin "2") (pinfunction "NC_2") (pintype "passive"))
    )
    (net (code "88") (name "unconnected-(Relay4-NC-Pad2)") (class "Default")
      (node (ref "Relay4") (pin "2") (pinfunction "NC_2") (pintype "passive"))
    )
    (net (code "89") (name "unconnected-(Relay5-NC-Pad2)") (class "Default")
      (node (ref "Relay5") (pin "2") (pinfunction "NC_2") (pintype "passive"))
    )
    (net (code "90") (name "unconnected-(Relay6-NC-Pad2)") (class "Default")
      (node (ref "Relay6") (pin "2") (pinfunction "NC_2") (pintype "passive"))
    )
    (net (code "91") (name "unconnected-(Relay7-NC-Pad2)") (class "Default")
      (node (ref "Relay7") (pin "2") (pinfunction "NC_2") (pintype "passive"))
    )
    (net (code "92") (name "unconnected-(Relay8-NC-Pad2)") (class "Default")
      (node (ref "Relay8") (pin "2") (pinfunction "NC_2") (pintype "passive"))
    )
    (net (code "93") (name "unconnected-(Relay9-NC-Pad2)") (class "Default")
      (node (ref "Relay9") (pin "2") (pinfunction "NC_2") (pintype "passive"))
    )
    (net (code "94") (name "unconnected-(Relay10-NC-Pad2)") (class "Default")
      (node (ref "Relay10") (pin "2") (pinfunction "NC_2") (pintype "passive"))
    )
  )
)
